# Son_of_Dark_Powersch.net
KiCad netlist of a schematic drawn in EAGLE
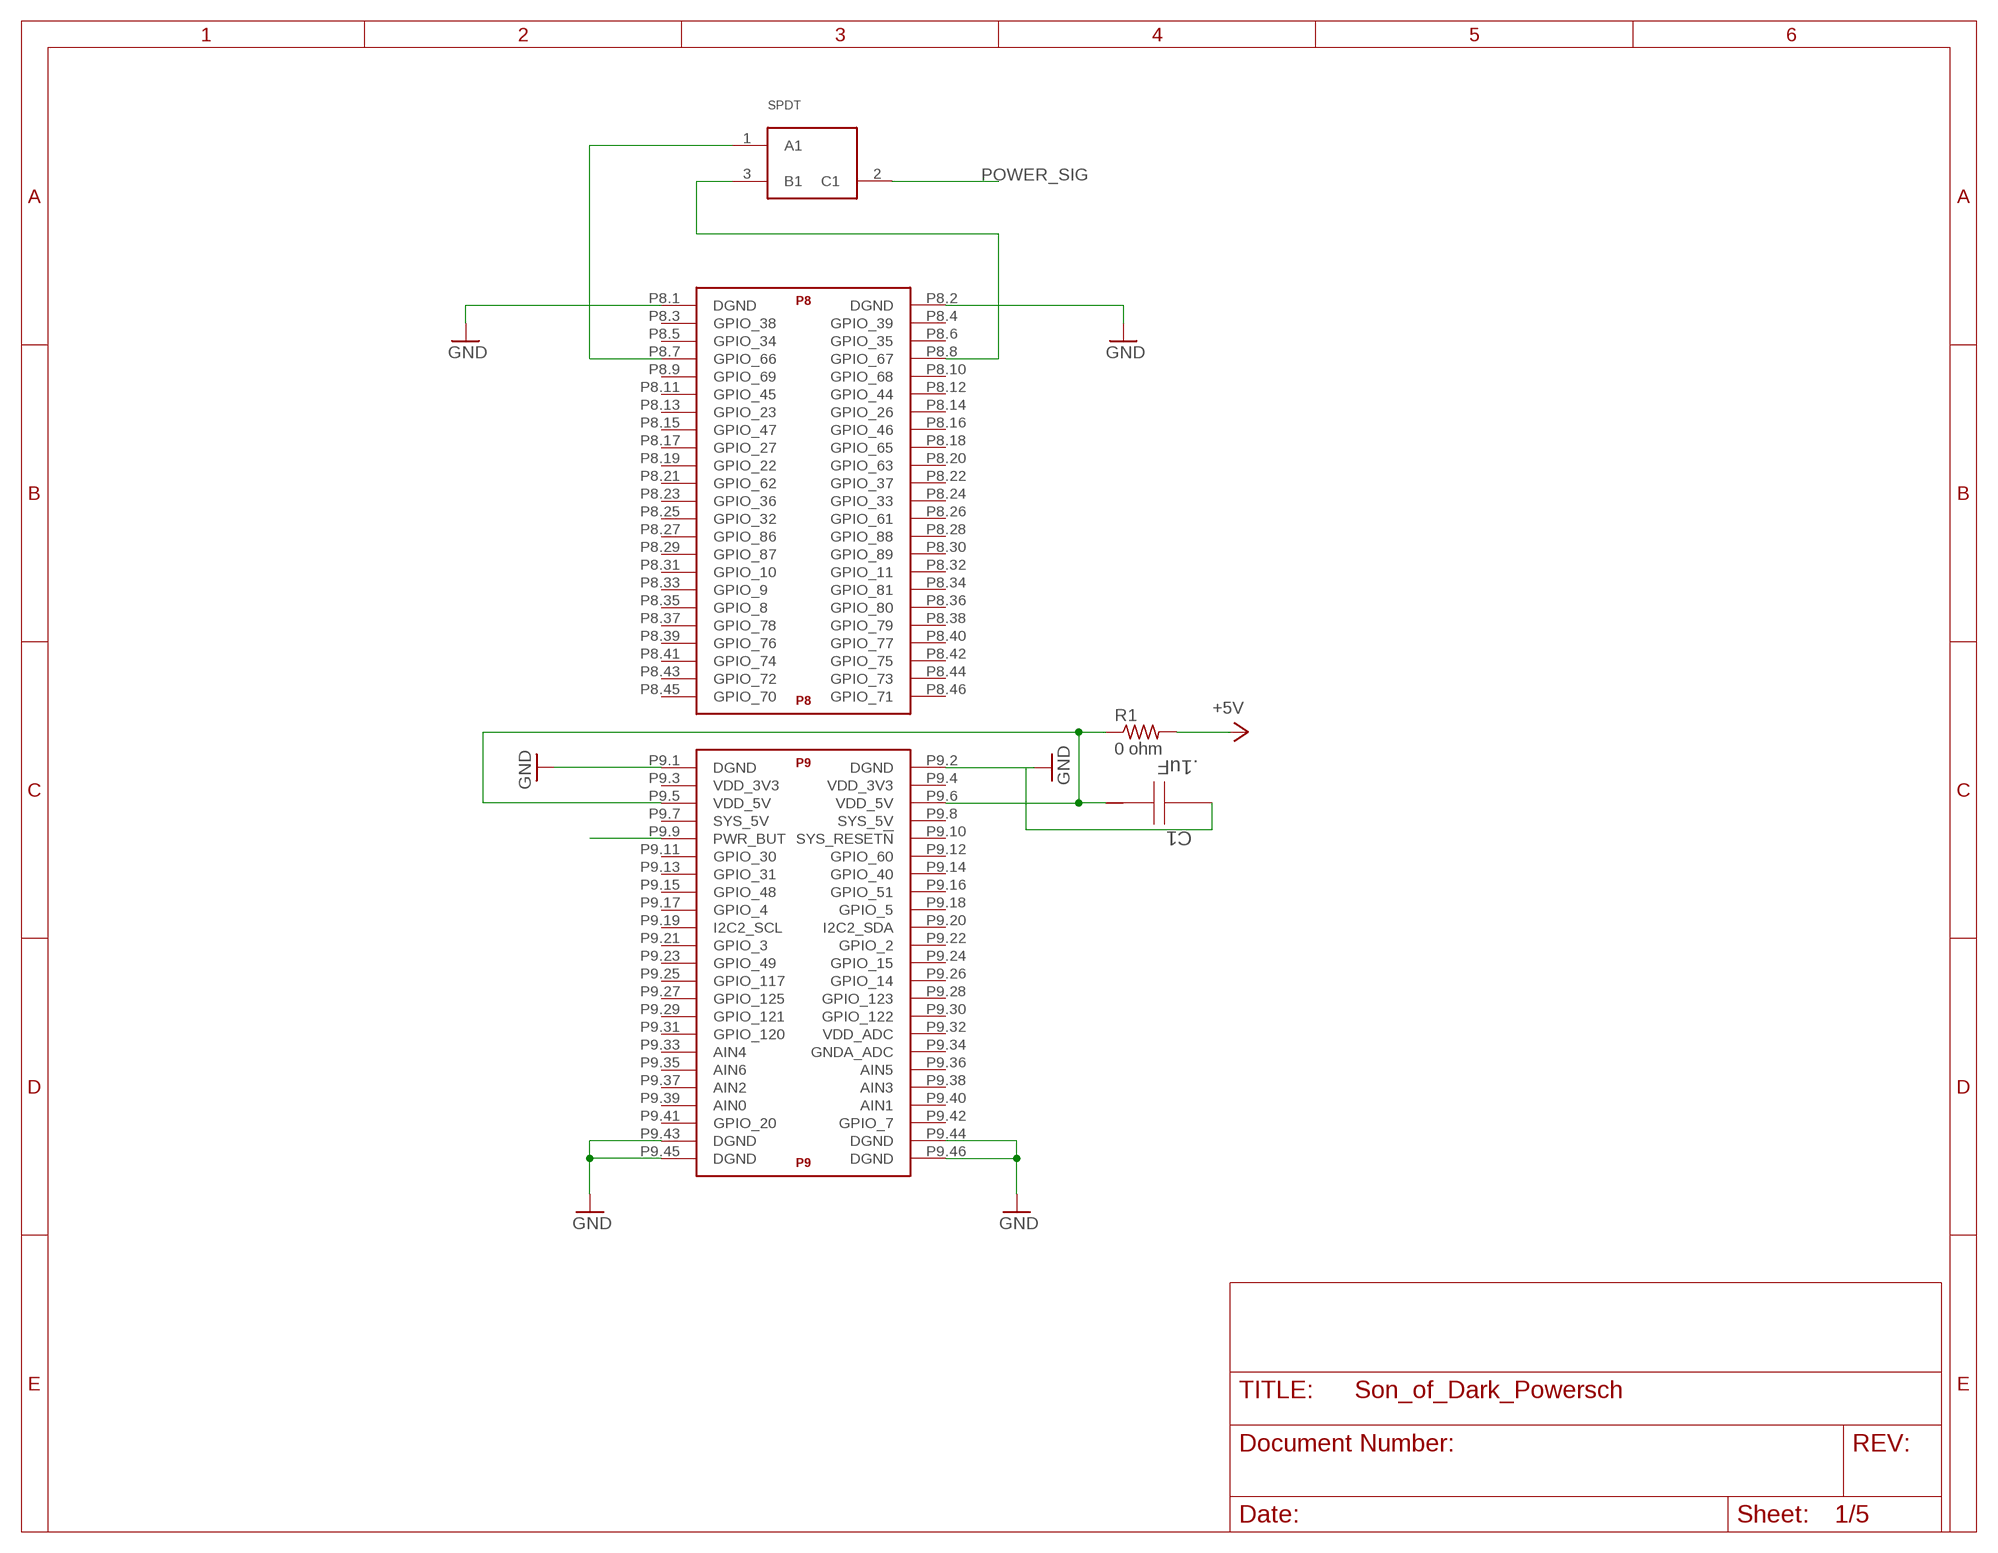
[diagram p0: schematic, sheet 1]
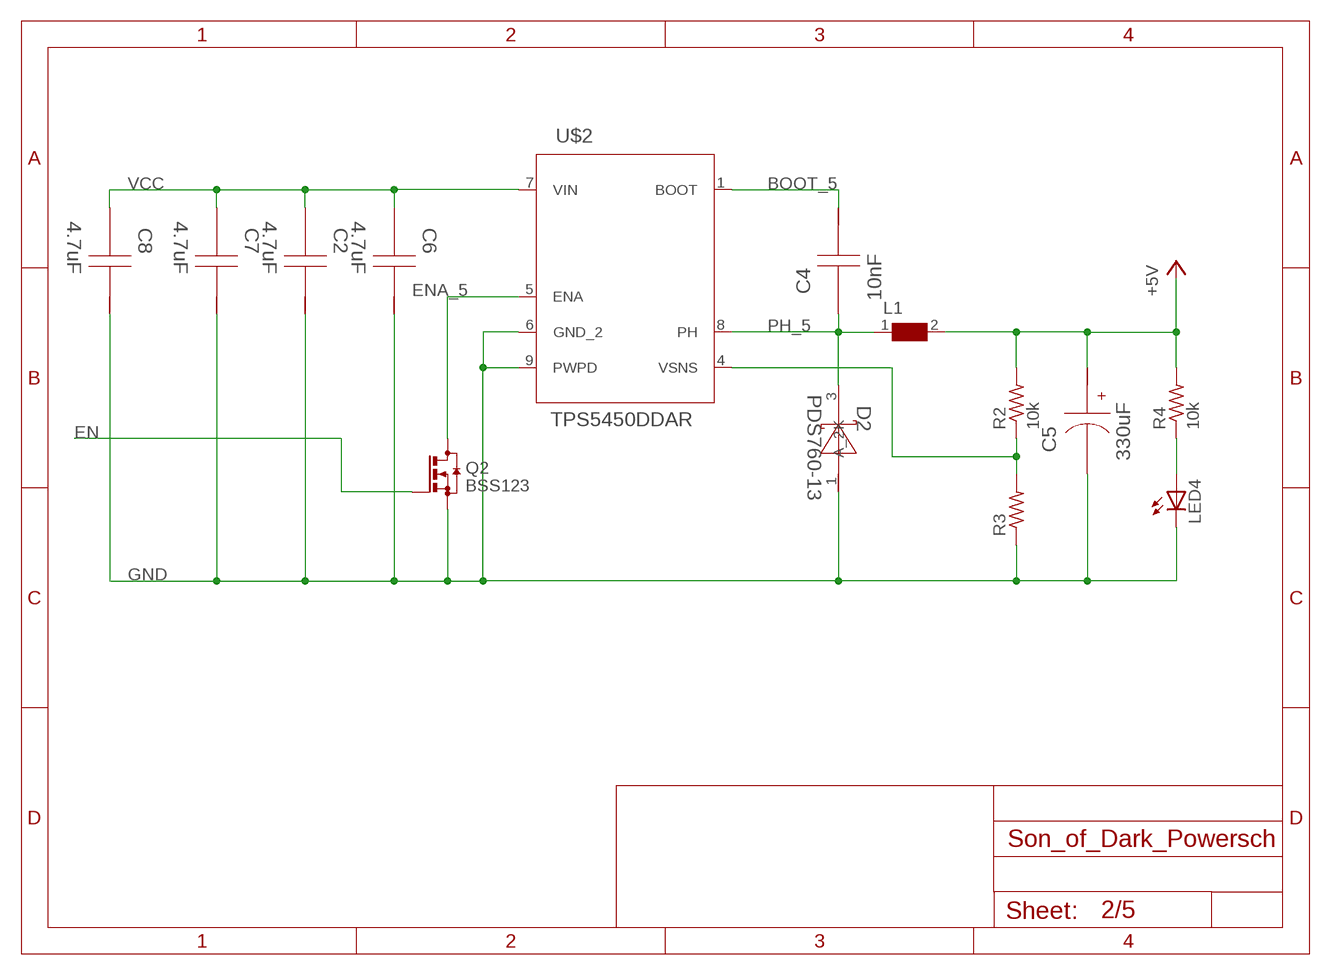
[diagram p1: schematic, sheet 2]
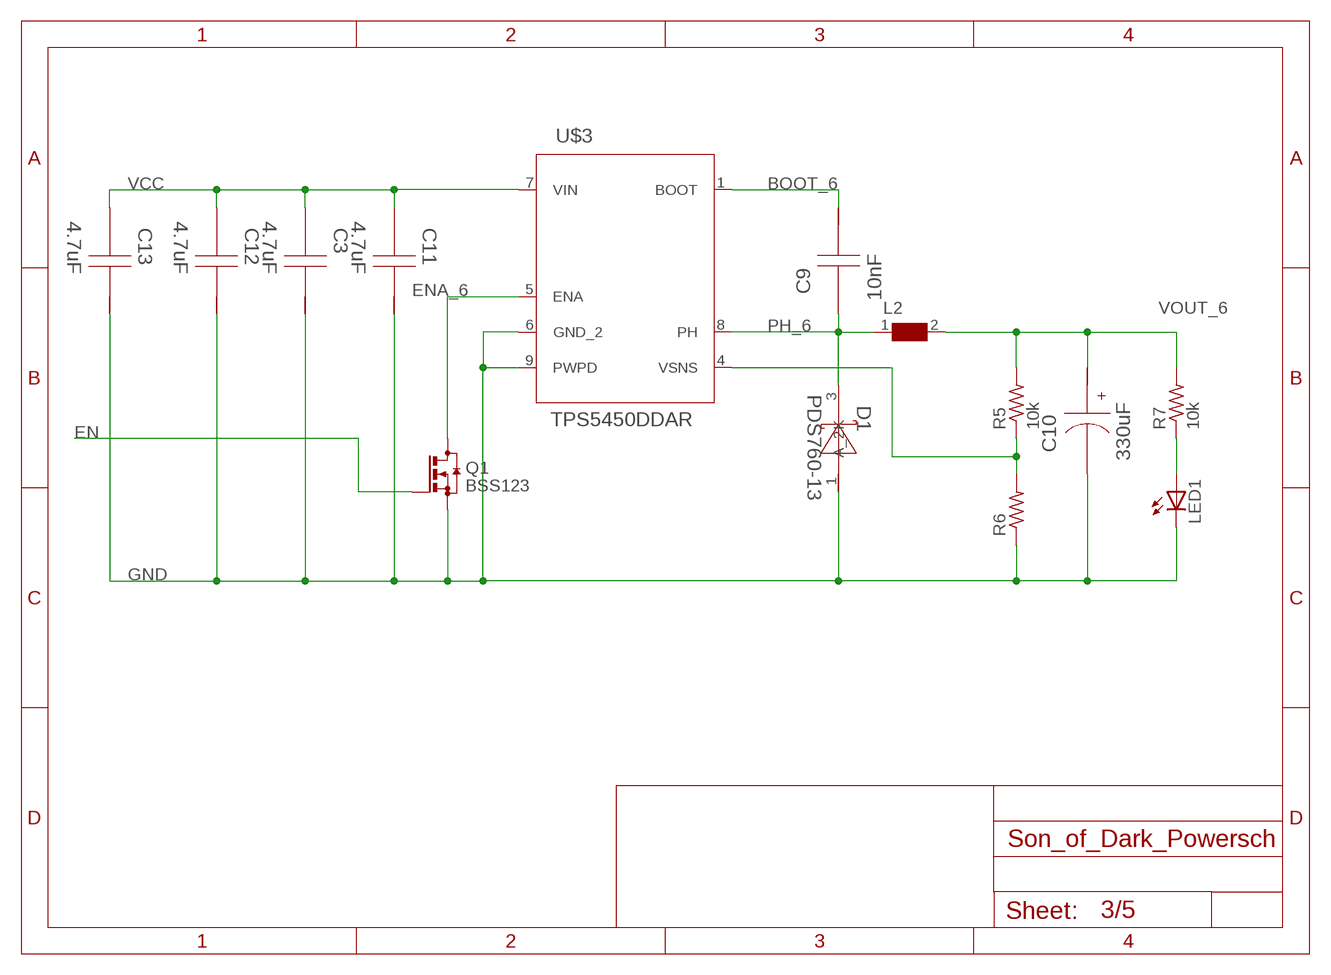
[diagram p2: schematic, sheet 3]
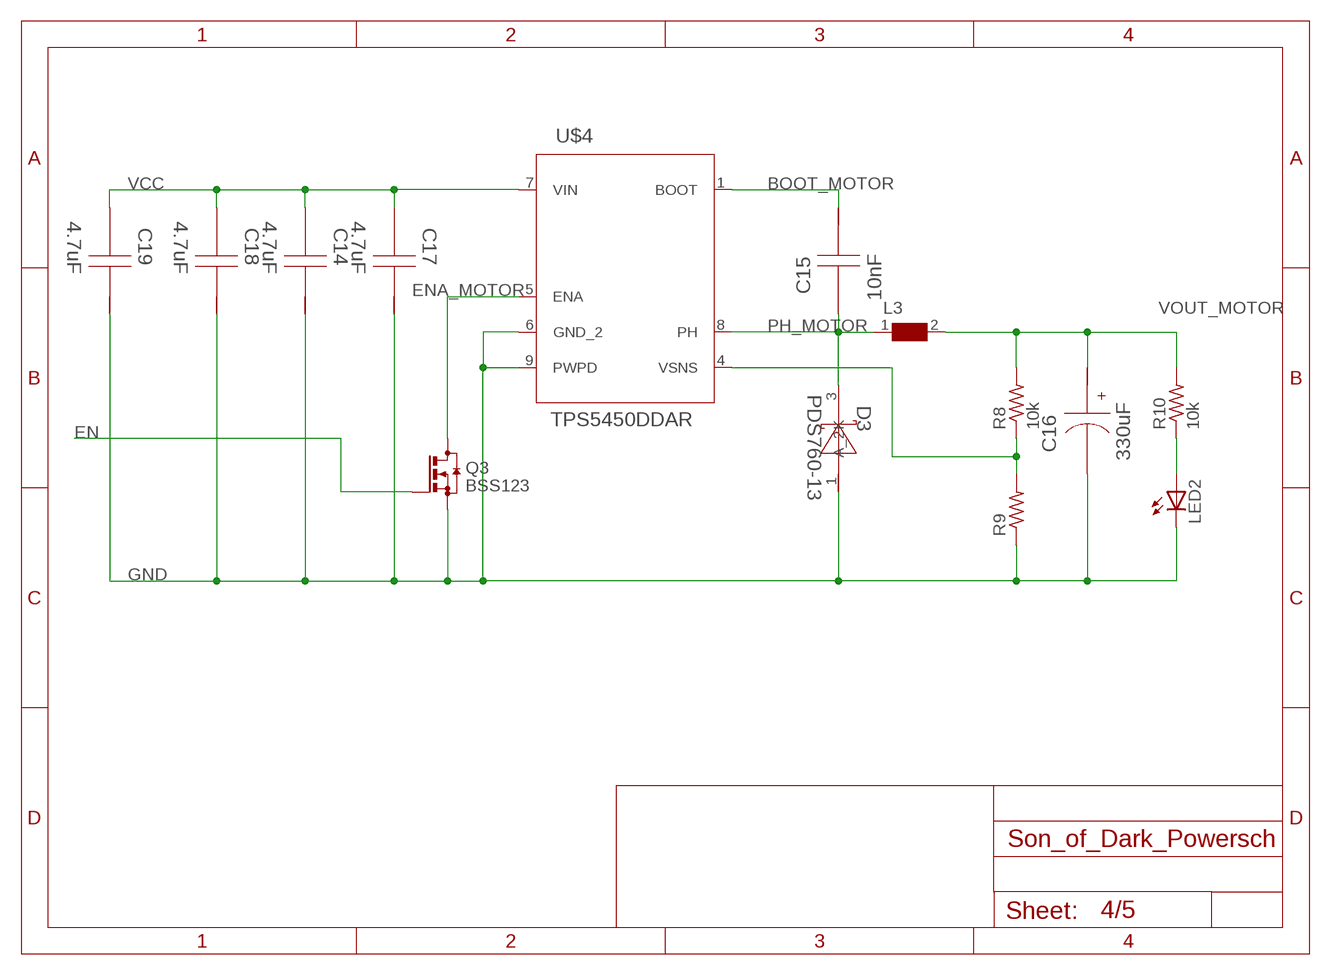
[diagram p3: schematic, sheet 4]
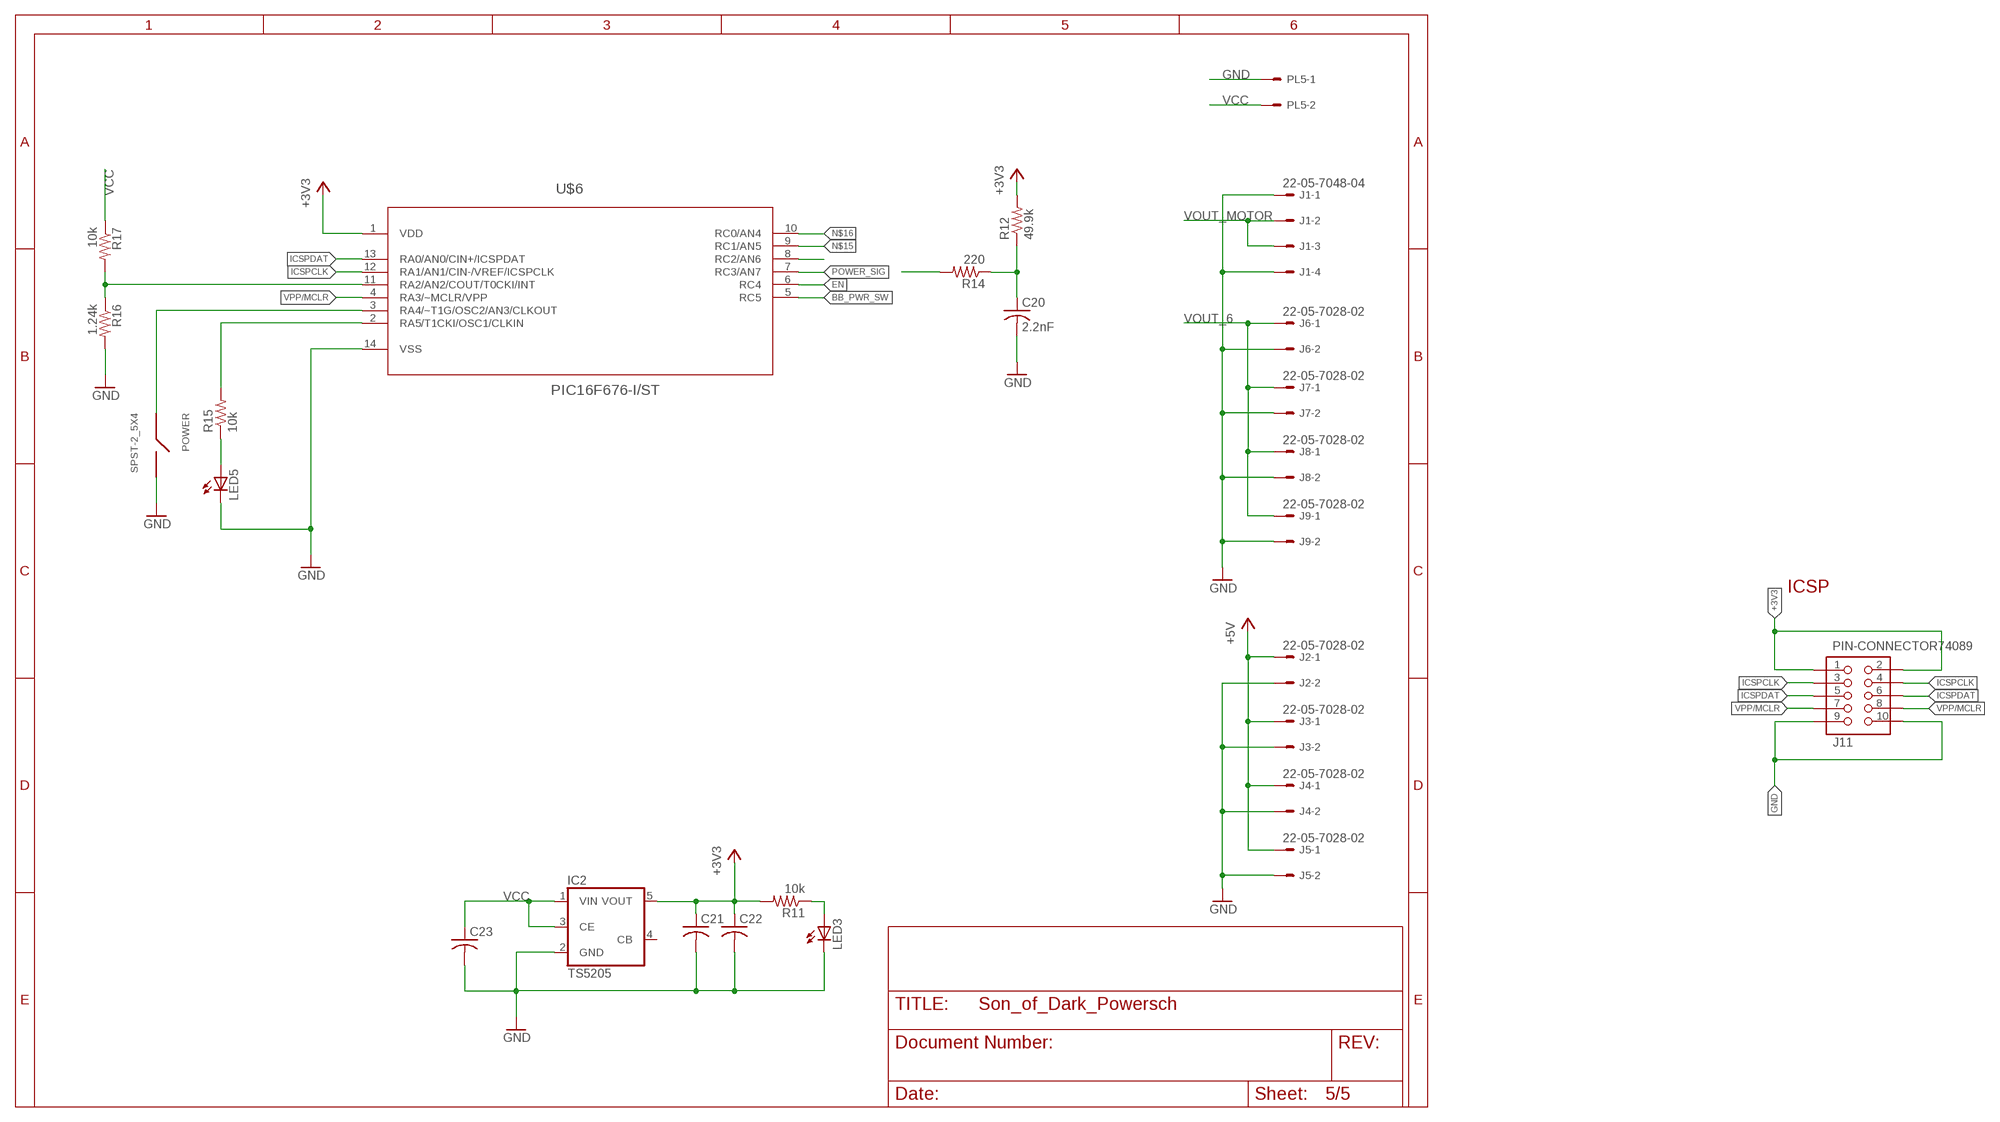
[diagram p4: schematic, sheet 5]

(export (version "E")
  (design (tool "Eeschema 10.0.6"))
  (components
    (comp (ref "C2")
      (value "4.7uF")
      (footprint "eagle-import:1206")
      (fields (field (name "MANUFACTURER_PART_NUMBER") "GRM31CR71H475KA12L"))
      (libsource (lib "eagle-import") (part "GRM31CR71H475KA12L"))
    )
    (comp (ref "C4")
      (value "10nF")
      (footprint "eagle-import:0805")
      (fields (field (name "MANUFACTURER_PART_NUMBER") "C0805C103K5RACTU"))
      (libsource (lib "eagle-import") (part "C0805C103K5RACTU"))
    )
    (comp (ref "C5")
      (value "330uF")
      (footprint "eagle-import:SM_RADIAL_10AMM")
      (fields (field (name "MANUFACTURER_PART_NUMBER") "10SVP330MX"))
      (libsource (lib "eagle-import") (part "10SVP330MX"))
    )
    (comp (ref "C6")
      (value "4.7uF")
      (footprint "eagle-import:1206")
      (fields (field (name "MANUFACTURER_PART_NUMBER") "GRM31CR71H475KA12L"))
      (libsource (lib "eagle-import") (part "GRM31CR71H475KA12L"))
    )
    (comp (ref "C7")
      (value "4.7uF")
      (footprint "eagle-import:1206")
      (fields (field (name "MANUFACTURER_PART_NUMBER") "GRM31CR71H475KA12L"))
      (libsource (lib "eagle-import") (part "GRM31CR71H475KA12L"))
    )
    (comp (ref "C8")
      (value "4.7uF")
      (footprint "eagle-import:1206")
      (fields (field (name "MANUFACTURER_PART_NUMBER") "GRM31CR71H475KA12L"))
      (libsource (lib "eagle-import") (part "GRM31CR71H475KA12L"))
    )
    (comp (ref "D2")
      (value "PDS760-13")
      (footprint "eagle-import:POWERDI5")
      (libsource (lib "eagle-import") (part "PDS760-13"))
    )
    (comp (ref "L1")
      (value "WE-HCC-7443331000_1090")
      (footprint "eagle-import:WE-HCC_1090")
      (fields (field (name "MPN") "7443331000"))
      (libsource (lib "eagle-import") (part "WE-HCC_1090-7443331000"))
    )
    (comp (ref "LED4")
      (value "LEDSML1206")
      (footprint "eagle-import:SML1206")
      (libsource (lib "eagle-import") (part "LEDSML1206"))
    )
    (comp (ref "Q2")
      (value "BSS123")
      (footprint "eagle-import:SOT23")
      (libsource (lib "eagle-import") (part "BSS123"))
    )
    (comp (ref "R2")
      (value "10k")
      (footprint "eagle-import:R1206")
      (libsource (lib "eagle-import") (part "R-US_R1206"))
    )
    (comp (ref "R3")
      (value "R-US_R1206")
      (footprint "eagle-import:R1206")
      (libsource (lib "eagle-import") (part "R-US_R1206"))
    )
    (comp (ref "R4")
      (value "10k")
      (footprint "eagle-import:R1206")
      (libsource (lib "eagle-import") (part "R-US_R1206"))
    )
    (comp (ref "U$2")
      (value "TPS5450DDAR")
      (footprint "eagle-import:R-PDSO-G8")
      (fields (field (name "MANUFACTURER_PART_NUMBER") "TPS5450DDA"))
      (libsource (lib "eagle-import") (part "TPS5450DDAR"))
    )
    (comp (ref "C3")
      (value "4.7uF")
      (footprint "eagle-import:1206")
      (fields (field (name "MANUFACTURER_PART_NUMBER") "GRM31CR71H475KA12L"))
      (libsource (lib "eagle-import") (part "GRM31CR71H475KA12L"))
    )
    (comp (ref "C9")
      (value "10nF")
      (footprint "eagle-import:0805")
      (fields (field (name "MANUFACTURER_PART_NUMBER") "C0805C103K5RACTU"))
      (libsource (lib "eagle-import") (part "C0805C103K5RACTU"))
    )
    (comp (ref "C10")
      (value "330uF")
      (footprint "eagle-import:SM_RADIAL_10AMM")
      (fields (field (name "MANUFACTURER_PART_NUMBER") "10SVP330MX"))
      (libsource (lib "eagle-import") (part "10SVP330MX"))
    )
    (comp (ref "C11")
      (value "4.7uF")
      (footprint "eagle-import:1206")
      (fields (field (name "MANUFACTURER_PART_NUMBER") "GRM31CR71H475KA12L"))
      (libsource (lib "eagle-import") (part "GRM31CR71H475KA12L"))
    )
    (comp (ref "C12")
      (value "4.7uF")
      (footprint "eagle-import:1206")
      (fields (field (name "MANUFACTURER_PART_NUMBER") "GRM31CR71H475KA12L"))
      (libsource (lib "eagle-import") (part "GRM31CR71H475KA12L"))
    )
    (comp (ref "C13")
      (value "4.7uF")
      (footprint "eagle-import:1206")
      (fields (field (name "MANUFACTURER_PART_NUMBER") "GRM31CR71H475KA12L"))
      (libsource (lib "eagle-import") (part "GRM31CR71H475KA12L"))
    )
    (comp (ref "D1")
      (value "PDS760-13")
      (footprint "eagle-import:POWERDI5")
      (libsource (lib "eagle-import") (part "PDS760-13"))
    )
    (comp (ref "L2")
      (value "WE-HCC-7443331000_1090")
      (footprint "eagle-import:WE-HCC_1090")
      (fields (field (name "MPN") "7443331000"))
      (libsource (lib "eagle-import") (part "WE-HCC_1090-7443331000"))
    )
    (comp (ref "LED1")
      (value "LEDSML1206")
      (footprint "eagle-import:SML1206")
      (libsource (lib "eagle-import") (part "LEDSML1206"))
    )
    (comp (ref "Q1")
      (value "BSS123")
      (footprint "eagle-import:SOT23")
      (libsource (lib "eagle-import") (part "BSS123"))
    )
    (comp (ref "R5")
      (value "10k")
      (footprint "eagle-import:R1206")
      (libsource (lib "eagle-import") (part "R-US_R1206"))
    )
    (comp (ref "R6")
      (value "R-US_R1206")
      (footprint "eagle-import:R1206")
      (libsource (lib "eagle-import") (part "R-US_R1206"))
    )
    (comp (ref "R7")
      (value "10k")
      (footprint "eagle-import:R1206")
      (libsource (lib "eagle-import") (part "R-US_R1206"))
    )
    (comp (ref "U$3")
      (value "TPS5450DDAR")
      (footprint "eagle-import:R-PDSO-G8")
      (fields (field (name "MANUFACTURER_PART_NUMBER") "TPS5450DDA"))
      (libsource (lib "eagle-import") (part "TPS5450DDAR"))
    )
    (comp (ref "C20")
      (value "2.2nF")
      (footprint "eagle-import:C0603")
      (libsource (lib "eagle-import") (part "C-USC0603"))
    )
    (comp (ref "C21")
      (value "C-USC0603")
      (footprint "eagle-import:C0603")
      (libsource (lib "eagle-import") (part "C-USC0603"))
    )
    (comp (ref "C22")
      (value "C-USC0603")
      (footprint "eagle-import:C0603")
      (libsource (lib "eagle-import") (part "C-USC0603"))
    )
    (comp (ref "C23")
      (value "C-USC0603")
      (footprint "eagle-import:C0603")
      (libsource (lib "eagle-import") (part "C-USC0603"))
    )
    (comp (ref "IC2")
      (value "TS5205")
      (footprint "eagle-import:SOT25")
      (libsource (lib "eagle-import") (part "TS5205"))
    )
    (comp (ref "J1")
      (value "22-05-7048-04")
      (footprint "eagle-import:7395-04")
      (libsource (lib "eagle-import") (part "22-?-0405-7048"))
    )
    (comp (ref "J2")
      (value "22-05-7028-02")
      (footprint "eagle-import:7395-02")
      (libsource (lib "eagle-import") (part "22-?-0205-7028"))
    )
    (comp (ref "J3")
      (value "22-05-7028-02")
      (footprint "eagle-import:7395-02")
      (libsource (lib "eagle-import") (part "22-?-0205-7028"))
    )
    (comp (ref "J4")
      (value "22-05-7028-02")
      (footprint "eagle-import:7395-02")
      (libsource (lib "eagle-import") (part "22-?-0205-7028"))
    )
    (comp (ref "J5")
      (value "22-05-7028-02")
      (footprint "eagle-import:7395-02")
      (libsource (lib "eagle-import") (part "22-?-0205-7028"))
    )
    (comp (ref "J6")
      (value "22-05-7028-02")
      (footprint "eagle-import:7395-02")
      (libsource (lib "eagle-import") (part "22-?-0205-7028"))
    )
    (comp (ref "J7")
      (value "22-05-7028-02")
      (footprint "eagle-import:7395-02")
      (libsource (lib "eagle-import") (part "22-?-0205-7028"))
    )
    (comp (ref "J8")
      (value "22-05-7028-02")
      (footprint "eagle-import:7395-02")
      (libsource (lib "eagle-import") (part "22-?-0205-7028"))
    )
    (comp (ref "J9")
      (value "22-05-7028-02")
      (footprint "eagle-import:7395-02")
      (libsource (lib "eagle-import") (part "22-?-0205-7028"))
    )
    (comp (ref "J11")
      (value "PIN-CONNECTOR74089")
      (footprint "eagle-import:10-PIN-SMD")
      (libsource (lib "eagle-import") (part "PIN-CONNECTOR74089"))
    )
    (comp (ref "LED3")
      (value "LEDSML1206")
      (footprint "eagle-import:SML1206")
      (libsource (lib "eagle-import") (part "LEDSML1206"))
    )
    (comp (ref "LED5")
      (value "LEDSML1206")
      (footprint "eagle-import:SML1206")
      (libsource (lib "eagle-import") (part "LEDSML1206"))
    )
    (comp (ref "PL5")
      (value "555X-2H")
      (footprint "eagle-import:5569-2")
      (libsource (lib "eagle-import") (part "555X-2H"))
    )
    (comp (ref "POWER")
      (value "SPST-2_5X4")
      (footprint "eagle-import:SPST-TAC-4X2_5MM")
      (libsource (lib "eagle-import") (part "SPST-2_5X4"))
    )
    (comp (ref "R11")
      (value "10k")
      (footprint "eagle-import:R1206")
      (libsource (lib "eagle-import") (part "R-US_R1206"))
    )
    (comp (ref "R12")
      (value "49.9k")
      (footprint "eagle-import:R0603")
      (libsource (lib "eagle-import") (part "R-US_R0603"))
    )
    (comp (ref "R14")
      (value "220")
      (footprint "eagle-import:R0603")
      (libsource (lib "eagle-import") (part "R-US_R0603"))
    )
    (comp (ref "R15")
      (value "10k")
      (footprint "eagle-import:R1206")
      (libsource (lib "eagle-import") (part "R-US_R1206"))
    )
    (comp (ref "R16")
      (value "1.24k")
      (footprint "eagle-import:R0603")
      (libsource (lib "eagle-import") (part "R-US_R0603"))
    )
    (comp (ref "R17")
      (value "10k")
      (footprint "eagle-import:R0603")
      (libsource (lib "eagle-import") (part "R-US_R0603"))
    )
    (comp (ref "U$6")
      (value "PIC16F676-I/ST")
      (footprint "eagle-import:SOP65P640X120-14N")
      (libsource (lib "eagle-import") (part "PIC16F676-I/ST"))
    )
    (comp (ref "C1")
      (value ".1uF")
      (footprint "eagle-import:1206")
      (fields (field (name "MANUFACTURER_PART_NUMBER") "C3216X5R1A106K"))
      (libsource (lib "eagle-import") (part "C3216X5R1A106K"))
    )
    (comp (ref "R1")
      (value "0 ohm")
      (footprint "eagle-import:R1206")
      (libsource (lib "eagle-import") (part "R-US_R1206"))
    )
    (comp (ref "SPDT")
      (value "SPDT_SWITCH")
      (footprint "eagle-import:SPDT")
      (libsource (lib "eagle-import") (part "SPDT_SWITCH"))
    )
    (comp (ref "U$1")
      (value "BEAGLE_BONE_BLACK_CAPE")
      (footprint "eagle-import:BEAGLE_BONE_BLACK_CAPE")
      (libsource (lib "eagle-import") (part "BEAGLE_BONE_BLACK_CAPE"))
    )
    (comp (ref "C14")
      (value "4.7uF")
      (footprint "eagle-import:1206")
      (fields (field (name "MANUFACTURER_PART_NUMBER") "GRM31CR71H475KA12L"))
      (libsource (lib "eagle-import") (part "GRM31CR71H475KA12L"))
    )
    (comp (ref "C15")
      (value "10nF")
      (footprint "eagle-import:0805")
      (fields (field (name "MANUFACTURER_PART_NUMBER") "C0805C103K5RACTU"))
      (libsource (lib "eagle-import") (part "C0805C103K5RACTU"))
    )
    (comp (ref "C16")
      (value "330uF")
      (footprint "eagle-import:SM_RADIAL_10AMM")
      (fields (field (name "MANUFACTURER_PART_NUMBER") "10SVP330MX"))
      (libsource (lib "eagle-import") (part "10SVP330MX"))
    )
    (comp (ref "C17")
      (value "4.7uF")
      (footprint "eagle-import:1206")
      (fields (field (name "MANUFACTURER_PART_NUMBER") "GRM31CR71H475KA12L"))
      (libsource (lib "eagle-import") (part "GRM31CR71H475KA12L"))
    )
    (comp (ref "C18")
      (value "4.7uF")
      (footprint "eagle-import:1206")
      (fields (field (name "MANUFACTURER_PART_NUMBER") "GRM31CR71H475KA12L"))
      (libsource (lib "eagle-import") (part "GRM31CR71H475KA12L"))
    )
    (comp (ref "C19")
      (value "4.7uF")
      (footprint "eagle-import:1206")
      (fields (field (name "MANUFACTURER_PART_NUMBER") "GRM31CR71H475KA12L"))
      (libsource (lib "eagle-import") (part "GRM31CR71H475KA12L"))
    )
    (comp (ref "D3")
      (value "PDS760-13")
      (footprint "eagle-import:POWERDI5")
      (libsource (lib "eagle-import") (part "PDS760-13"))
    )
    (comp (ref "L3")
      (value "WE-HCC-7443331000_1090")
      (footprint "eagle-import:WE-HCC_1090")
      (fields (field (name "MPN") "7443331000"))
      (libsource (lib "eagle-import") (part "WE-HCC_1090-7443331000"))
    )
    (comp (ref "LED2")
      (value "LEDSML1206")
      (footprint "eagle-import:SML1206")
      (libsource (lib "eagle-import") (part "LEDSML1206"))
    )
    (comp (ref "Q3")
      (value "BSS123")
      (footprint "eagle-import:SOT23")
      (libsource (lib "eagle-import") (part "BSS123"))
    )
    (comp (ref "R8")
      (value "10k")
      (footprint "eagle-import:R1206")
      (libsource (lib "eagle-import") (part "R-US_R1206"))
    )
    (comp (ref "R9")
      (value "R-US_R1206")
      (footprint "eagle-import:R1206")
      (libsource (lib "eagle-import") (part "R-US_R1206"))
    )
    (comp (ref "R10")
      (value "10k")
      (footprint "eagle-import:R1206")
      (libsource (lib "eagle-import") (part "R-US_R1206"))
    )
    (comp (ref "U$4")
      (value "TPS5450DDAR")
      (footprint "eagle-import:R-PDSO-G8")
      (fields (field (name "MANUFACTURER_PART_NUMBER") "TPS5450DDA"))
      (libsource (lib "eagle-import") (part "TPS5450DDAR"))
    )
  )
  (nets
    (net (code "1") (name "+3V3") (class "Default")
      (node (ref "C21") (pin "1") (pinfunction "1_1") (pintype "passive"))
      (node (ref "C22") (pin "1") (pinfunction "1_1") (pintype "passive"))
      (node (ref "IC2") (pin "5") (pinfunction "VOUT_5") (pintype "passive"))
      (node (ref "J11") (pin "1") (pinfunction "P$1_1") (pintype "power_in"))
      (node (ref "J11") (pin "2") (pinfunction "P$2_2") (pintype "power_in"))
      (node (ref "R11") (pin "2") (pinfunction "2_2") (pintype "passive"))
      (node (ref "R12") (pin "2") (pinfunction "2_2") (pintype "passive"))
      (node (ref "U$6") (pin "1") (pinfunction "VDD_1") (pintype "power_in"))
    )
    (net (code "2") (name "+5V") (class "Default")
      (node (ref "C5") (pin "1") (pinfunction "+_1") (pintype "passive"))
      (node (ref "J2") (pin "1") (pinfunction "S_1") (pintype "passive"))
      (node (ref "J3") (pin "1") (pinfunction "S_1") (pintype "passive"))
      (node (ref "J4") (pin "1") (pinfunction "S_1") (pintype "passive"))
      (node (ref "J5") (pin "1") (pinfunction "S_1") (pintype "passive"))
      (node (ref "L1") (pin "2") (pinfunction "2_2") (pintype "passive"))
      (node (ref "R1") (pin "2") (pinfunction "2_2") (pintype "passive"))
      (node (ref "R2") (pin "2") (pinfunction "2_2") (pintype "passive"))
      (node (ref "R4") (pin "2") (pinfunction "2_2") (pintype "passive"))
    )
    (net (code "3") (name "BB_PWR_SW") (class "Default")
      (node (ref "U$1") (pin "P9.9") (pinfunction "PWR_BUT_P9.9") (pintype "bidirectional"))
      (node (ref "U$6") (pin "5") (pinfunction "RC5_5") (pintype "bidirectional"))
    )
    (net (code "4") (name "BOOT_5") (class "Default")
      (node (ref "C4") (pin "1") (pinfunction "1_1") (pintype "passive"))
      (node (ref "U$2") (pin "1") (pinfunction "BOOT_1") (pintype "passive"))
    )
    (net (code "5") (name "BOOT_6") (class "Default")
      (node (ref "C9") (pin "1") (pinfunction "1_1") (pintype "passive"))
      (node (ref "U$3") (pin "1") (pinfunction "BOOT_1") (pintype "passive"))
    )
    (net (code "6") (name "BOOT_MOTOR") (class "Default")
      (node (ref "C15") (pin "1") (pinfunction "1_1") (pintype "passive"))
      (node (ref "U$4") (pin "1") (pinfunction "BOOT_1") (pintype "passive"))
    )
    (net (code "7") (name "EN") (class "Default")
      (node (ref "Q1") (pin "1") (pinfunction "G_1") (pintype "passive"))
      (node (ref "Q2") (pin "1") (pinfunction "G_1") (pintype "passive"))
      (node (ref "Q3") (pin "1") (pinfunction "G_1") (pintype "passive"))
      (node (ref "U$6") (pin "6") (pinfunction "RC4_6") (pintype "bidirectional"))
    )
    (net (code "8") (name "ENA_5") (class "Default")
      (node (ref "Q2") (pin "3") (pinfunction "D_3") (pintype "passive"))
      (node (ref "U$2") (pin "5") (pinfunction "ENA_5") (pintype "passive"))
    )
    (net (code "9") (name "ENA_6") (class "Default")
      (node (ref "Q1") (pin "3") (pinfunction "D_3") (pintype "passive"))
      (node (ref "U$3") (pin "5") (pinfunction "ENA_5") (pintype "passive"))
    )
    (net (code "10") (name "ENA_MOTOR") (class "Default")
      (node (ref "Q3") (pin "3") (pinfunction "D_3") (pintype "passive"))
      (node (ref "U$4") (pin "5") (pinfunction "ENA_5") (pintype "passive"))
    )
    (net (code "11") (name "GND") (class "Default")
      (node (ref "C1") (pin "2") (pinfunction "2_2") (pintype "passive"))
      (node (ref "C10") (pin "2") (pinfunction "-_2") (pintype "passive"))
      (node (ref "C11") (pin "1") (pinfunction "1_1") (pintype "passive"))
      (node (ref "C12") (pin "1") (pinfunction "1_1") (pintype "passive"))
      (node (ref "C13") (pin "1") (pinfunction "1_1") (pintype "passive"))
      (node (ref "C14") (pin "1") (pinfunction "1_1") (pintype "passive"))
      (node (ref "C16") (pin "2") (pinfunction "-_2") (pintype "passive"))
      (node (ref "C17") (pin "1") (pinfunction "1_1") (pintype "passive"))
      (node (ref "C18") (pin "1") (pinfunction "1_1") (pintype "passive"))
      (node (ref "C19") (pin "1") (pinfunction "1_1") (pintype "passive"))
      (node (ref "C2") (pin "1") (pinfunction "1_1") (pintype "passive"))
      (node (ref "C20") (pin "2") (pinfunction "2_2") (pintype "passive"))
      (node (ref "C21") (pin "2") (pinfunction "2_2") (pintype "passive"))
      (node (ref "C22") (pin "2") (pinfunction "2_2") (pintype "passive"))
      (node (ref "C23") (pin "2") (pinfunction "2_2") (pintype "passive"))
      (node (ref "C3") (pin "1") (pinfunction "1_1") (pintype "passive"))
      (node (ref "C5") (pin "2") (pinfunction "-_2") (pintype "passive"))
      (node (ref "C6") (pin "1") (pinfunction "1_1") (pintype "passive"))
      (node (ref "C7") (pin "1") (pinfunction "1_1") (pintype "passive"))
      (node (ref "C8") (pin "1") (pinfunction "1_1") (pintype "passive"))
      (node (ref "D1") (pin "1") (pinfunction "A_2_1") (pintype "passive"))
      (node (ref "D2") (pin "1") (pinfunction "A_2_1") (pintype "passive"))
      (node (ref "D3") (pin "1") (pinfunction "A_2_1") (pintype "passive"))
      (node (ref "IC2") (pin "2") (pinfunction "GND_2") (pintype "passive"))
      (node (ref "J1") (pin "1") (pinfunction "S_1") (pintype "passive"))
      (node (ref "J1") (pin "4") (pinfunction "S_4") (pintype "passive"))
      (node (ref "J11") (pin "10") (pinfunction "P$10_10") (pintype "power_in"))
      (node (ref "J11") (pin "9") (pinfunction "P$9_9") (pintype "power_in"))
      (node (ref "J2") (pin "2") (pinfunction "S_2") (pintype "passive"))
      (node (ref "J3") (pin "2") (pinfunction "S_2") (pintype "passive"))
      (node (ref "J4") (pin "2") (pinfunction "S_2") (pintype "passive"))
      (node (ref "J5") (pin "2") (pinfunction "S_2") (pintype "passive"))
      (node (ref "J6") (pin "2") (pinfunction "S_2") (pintype "passive"))
      (node (ref "J7") (pin "2") (pinfunction "S_2") (pintype "passive"))
      (node (ref "J8") (pin "2") (pinfunction "S_2") (pintype "passive"))
      (node (ref "J9") (pin "2") (pinfunction "S_2") (pintype "passive"))
      (node (ref "LED1") (pin "C") (pinfunction "C_C") (pintype "passive"))
      (node (ref "LED2") (pin "C") (pinfunction "C_C") (pintype "passive"))
      (node (ref "LED3") (pin "C") (pinfunction "C_C") (pintype "passive"))
      (node (ref "LED4") (pin "C") (pinfunction "C_C") (pintype "passive"))
      (node (ref "LED5") (pin "C") (pinfunction "C_C") (pintype "passive"))
      (node (ref "PL5") (pin "1") (pinfunction "S_1") (pintype "passive"))
      (node (ref "POWER") (pin "P$2") (pinfunction "P$2_P$2") (pintype "bidirectional"))
      (node (ref "Q1") (pin "2") (pinfunction "S_2") (pintype "passive"))
      (node (ref "Q2") (pin "2") (pinfunction "S_2") (pintype "passive"))
      (node (ref "Q3") (pin "2") (pinfunction "S_2") (pintype "passive"))
      (node (ref "R16") (pin "2") (pinfunction "2_2") (pintype "passive"))
      (node (ref "R3") (pin "1") (pinfunction "1_1") (pintype "passive"))
      (node (ref "R6") (pin "1") (pinfunction "1_1") (pintype "passive"))
      (node (ref "R9") (pin "1") (pinfunction "1_1") (pintype "passive"))
      (node (ref "U$1") (pin "P8.1") (pinfunction "DGND_P8.1") (pintype "bidirectional"))
      (node (ref "U$1") (pin "P8.2") (pinfunction "DGND_P8.2") (pintype "bidirectional"))
      (node (ref "U$1") (pin "P9.1") (pinfunction "DGND_P9.1") (pintype "bidirectional"))
      (node (ref "U$1") (pin "P9.2") (pinfunction "DGND_P9.2") (pintype "bidirectional"))
      (node (ref "U$1") (pin "P9.43") (pinfunction "DGND_P9.43") (pintype "bidirectional"))
      (node (ref "U$1") (pin "P9.44") (pinfunction "DGND_P9.44") (pintype "bidirectional"))
      (node (ref "U$1") (pin "P9.45") (pinfunction "DGND_P9.45") (pintype "bidirectional"))
      (node (ref "U$1") (pin "P9.46") (pinfunction "DGND_P9.46") (pintype "bidirectional"))
      (node (ref "U$2") (pin "6") (pinfunction "GND_2_6") (pintype "passive"))
      (node (ref "U$2") (pin "9") (pinfunction "PWPD_9") (pintype "passive"))
      (node (ref "U$3") (pin "6") (pinfunction "GND_2_6") (pintype "passive"))
      (node (ref "U$3") (pin "9") (pinfunction "PWPD_9") (pintype "passive"))
      (node (ref "U$4") (pin "6") (pinfunction "GND_2_6") (pintype "passive"))
      (node (ref "U$4") (pin "9") (pinfunction "PWPD_9") (pintype "passive"))
      (node (ref "U$6") (pin "14") (pinfunction "VSS_14") (pintype "power_in"))
    )
    (net (code "12") (name "ICSPCLK") (class "Default")
      (node (ref "J11") (pin "3") (pinfunction "P$3_3") (pintype "power_in"))
      (node (ref "J11") (pin "4") (pinfunction "P$4_4") (pintype "power_in"))
      (node (ref "U$6") (pin "12") (pinfunction "RA1/AN1/CIN-/VREF/ICSPCLK_12") (pintype "bidirectional"))
    )
    (net (code "13") (name "ICSPDAT") (class "Default")
      (node (ref "J11") (pin "5") (pinfunction "P$5_5") (pintype "power_in"))
      (node (ref "J11") (pin "6") (pinfunction "P$6_6") (pintype "power_in"))
      (node (ref "U$6") (pin "13") (pinfunction "RA0/AN0/CIN+/ICSPDAT_13") (pintype "bidirectional"))
    )
    (net (code "14") (name "N$15") (class "Default")
      (node (ref "U$6") (pin "9") (pinfunction "RC1/AN5_9") (pintype "bidirectional"))
    )
    (net (code "15") (name "N$16") (class "Default")
      (node (ref "U$6") (pin "10") (pinfunction "RC0/AN4_10") (pintype "bidirectional"))
    )
    (net (code "16") (name "Net-(C1-Pad1)") (class "Default")
      (node (ref "C1") (pin "1") (pinfunction "1_1") (pintype "passive"))
      (node (ref "R1") (pin "1") (pinfunction "1_1") (pintype "passive"))
      (node (ref "U$1") (pin "P9.5") (pinfunction "VDD_5V_P9.5") (pintype "bidirectional"))
      (node (ref "U$1") (pin "P9.6") (pinfunction "VDD_5V_P9.6") (pintype "bidirectional"))
    )
    (net (code "17") (name "Net-(C20-Pad1)") (class "Default")
      (node (ref "C20") (pin "1") (pinfunction "1_1") (pintype "passive"))
      (node (ref "R12") (pin "1") (pinfunction "1_1") (pintype "passive"))
      (node (ref "R14") (pin "1") (pinfunction "1_1") (pintype "passive"))
    )
    (net (code "18") (name "Net-(LED1-PadA)") (class "Default")
      (node (ref "LED1") (pin "A") (pinfunction "A_A") (pintype "passive"))
      (node (ref "R7") (pin "1") (pinfunction "1_1") (pintype "passive"))
    )
    (net (code "19") (name "Net-(LED2-PadA)") (class "Default")
      (node (ref "LED2") (pin "A") (pinfunction "A_A") (pintype "passive"))
      (node (ref "R10") (pin "1") (pinfunction "1_1") (pintype "passive"))
    )
    (net (code "20") (name "Net-(LED3-PadA)") (class "Default")
      (node (ref "LED3") (pin "A") (pinfunction "A_A") (pintype "passive"))
      (node (ref "R11") (pin "1") (pinfunction "1_1") (pintype "passive"))
    )
    (net (code "21") (name "Net-(LED4-PadA)") (class "Default")
      (node (ref "LED4") (pin "A") (pinfunction "A_A") (pintype "passive"))
      (node (ref "R4") (pin "1") (pinfunction "1_1") (pintype "passive"))
    )
    (net (code "22") (name "Net-(LED5-PadA)") (class "Default")
      (node (ref "LED5") (pin "A") (pinfunction "A_A") (pintype "passive"))
      (node (ref "R15") (pin "1") (pinfunction "1_1") (pintype "passive"))
    )
    (net (code "23") (name "Net-(SPDT-A1)") (class "Default")
      (node (ref "SPDT") (pin "1") (pinfunction "A1_1") (pintype "bidirectional"))
      (node (ref "U$1") (pin "P8.7") (pinfunction "GPIO_66_P8.7") (pintype "bidirectional"))
    )
    (net (code "24") (name "Net-(SPDT-B1)") (class "Default")
      (node (ref "SPDT") (pin "3") (pinfunction "B1_3") (pintype "bidirectional"))
      (node (ref "U$1") (pin "P8.8") (pinfunction "GPIO_67_P8.8") (pintype "bidirectional"))
    )
    (net (code "25") (name "Net-(U$2-VSNS)") (class "Default")
      (node (ref "R2") (pin "1") (pinfunction "1_1") (pintype "passive"))
      (node (ref "R3") (pin "2") (pinfunction "2_2") (pintype "passive"))
      (node (ref "U$2") (pin "4") (pinfunction "VSNS_4") (pintype "passive"))
    )
    (net (code "26") (name "Net-(U$3-VSNS)") (class "Default")
      (node (ref "R5") (pin "1") (pinfunction "1_1") (pintype "passive"))
      (node (ref "R6") (pin "2") (pinfunction "2_2") (pintype "passive"))
      (node (ref "U$3") (pin "4") (pinfunction "VSNS_4") (pintype "passive"))
    )
    (net (code "27") (name "Net-(U$4-VSNS)") (class "Default")
      (node (ref "R8") (pin "1") (pinfunction "1_1") (pintype "passive"))
      (node (ref "R9") (pin "2") (pinfunction "2_2") (pintype "passive"))
      (node (ref "U$4") (pin "4") (pinfunction "VSNS_4") (pintype "passive"))
    )
    (net (code "28") (name "Net-(U$6-RA2{slash}AN2{slash}COUT{slash}T0CKI{slash}INT)") (class "Default")
      (node (ref "R16") (pin "1") (pinfunction "1_1") (pintype "passive"))
      (node (ref "R17") (pin "2") (pinfunction "2_2") (pintype "passive"))
      (node (ref "U$6") (pin "11") (pinfunction "RA2/AN2/COUT/T0CKI/INT_11") (pintype "bidirectional"))
    )
    (net (code "29") (name "Net-(U$6-RA4{slash}~{T1G{slash}OSC2{slash}AN3{slash}CLKOUT})") (class "Default")
      (node (ref "POWER") (pin "P$1") (pinfunction "P$1_P$1") (pintype "bidirectional"))
      (node (ref "U$6") (pin "3") (pinfunction "RA4/~{T1G/OSC2/AN3/CLKOUT}_3") (pintype "bidirectional"))
    )
    (net (code "30") (name "Net-(U$6-RA5{slash}T1CKI{slash}OSC1{slash}CLKIN)") (class "Default")
      (node (ref "R15") (pin "2") (pinfunction "2_2") (pintype "passive"))
      (node (ref "U$6") (pin "2") (pinfunction "RA5/T1CKI/OSC1/CLKIN_2") (pintype "bidirectional"))
    )
    (net (code "31") (name "PH_5") (class "Default")
      (node (ref "C4") (pin "2") (pinfunction "2_2") (pintype "passive"))
      (node (ref "D2") (pin "3") (pinfunction "K_3") (pintype "passive"))
      (node (ref "L1") (pin "1") (pinfunction "1_1") (pintype "passive"))
      (node (ref "U$2") (pin "8") (pinfunction "PH_8") (pintype "passive"))
    )
    (net (code "32") (name "PH_6") (class "Default")
      (node (ref "C9") (pin "2") (pinfunction "2_2") (pintype "passive"))
      (node (ref "D1") (pin "3") (pinfunction "K_3") (pintype "passive"))
      (node (ref "L2") (pin "1") (pinfunction "1_1") (pintype "passive"))
      (node (ref "U$3") (pin "8") (pinfunction "PH_8") (pintype "passive"))
    )
    (net (code "33") (name "PH_MOTOR") (class "Default")
      (node (ref "C15") (pin "2") (pinfunction "2_2") (pintype "passive"))
      (node (ref "D3") (pin "3") (pinfunction "K_3") (pintype "passive"))
      (node (ref "L3") (pin "1") (pinfunction "1_1") (pintype "passive"))
      (node (ref "U$4") (pin "8") (pinfunction "PH_8") (pintype "passive"))
    )
    (net (code "34") (name "POWER_SIG") (class "Default")
      (node (ref "SPDT") (pin "2") (pinfunction "C1_2") (pintype "bidirectional"))
      (node (ref "U$6") (pin "7") (pinfunction "RC3/AN7_7") (pintype "bidirectional"))
    )
    (net (code "35") (name "VCC") (class "Default")
      (node (ref "C11") (pin "2") (pinfunction "2_2") (pintype "passive"))
      (node (ref "C12") (pin "2") (pinfunction "2_2") (pintype "passive"))
      (node (ref "C13") (pin "2") (pinfunction "2_2") (pintype "passive"))
      (node (ref "C14") (pin "2") (pinfunction "2_2") (pintype "passive"))
      (node (ref "C17") (pin "2") (pinfunction "2_2") (pintype "passive"))
      (node (ref "C18") (pin "2") (pinfunction "2_2") (pintype "passive"))
      (node (ref "C19") (pin "2") (pinfunction "2_2") (pintype "passive"))
      (node (ref "C2") (pin "2") (pinfunction "2_2") (pintype "passive"))
      (node (ref "C23") (pin "1") (pinfunction "1_1") (pintype "passive"))
      (node (ref "C3") (pin "2") (pinfunction "2_2") (pintype "passive"))
      (node (ref "C6") (pin "2") (pinfunction "2_2") (pintype "passive"))
      (node (ref "C7") (pin "2") (pinfunction "2_2") (pintype "passive"))
      (node (ref "C8") (pin "2") (pinfunction "2_2") (pintype "passive"))
      (node (ref "IC2") (pin "1") (pinfunction "VIN_1") (pintype "input"))
      (node (ref "IC2") (pin "3") (pinfunction "CE_3") (pintype "input"))
      (node (ref "PL5") (pin "2") (pinfunction "S_2") (pintype "passive"))
      (node (ref "R17") (pin "1") (pinfunction "1_1") (pintype "passive"))
      (node (ref "U$2") (pin "7") (pinfunction "VIN_7") (pintype "passive"))
      (node (ref "U$3") (pin "7") (pinfunction "VIN_7") (pintype "passive"))
      (node (ref "U$4") (pin "7") (pinfunction "VIN_7") (pintype "passive"))
    )
    (net (code "36") (name "VOUT_6") (class "Default")
      (node (ref "C10") (pin "1") (pinfunction "+_1") (pintype "passive"))
      (node (ref "J6") (pin "1") (pinfunction "S_1") (pintype "passive"))
      (node (ref "J7") (pin "1") (pinfunction "S_1") (pintype "passive"))
      (node (ref "J8") (pin "1") (pinfunction "S_1") (pintype "passive"))
      (node (ref "J9") (pin "1") (pinfunction "S_1") (pintype "passive"))
      (node (ref "L2") (pin "2") (pinfunction "2_2") (pintype "passive"))
      (node (ref "R5") (pin "2") (pinfunction "2_2") (pintype "passive"))
      (node (ref "R7") (pin "2") (pinfunction "2_2") (pintype "passive"))
    )
    (net (code "37") (name "VOUT_MOTOR") (class "Default")
      (node (ref "C16") (pin "1") (pinfunction "+_1") (pintype "passive"))
      (node (ref "J1") (pin "2") (pinfunction "S_2") (pintype "passive"))
      (node (ref "J1") (pin "3") (pinfunction "S_3") (pintype "passive"))
      (node (ref "L3") (pin "2") (pinfunction "2_2") (pintype "passive"))
      (node (ref "R10") (pin "2") (pinfunction "2_2") (pintype "passive"))
      (node (ref "R8") (pin "2") (pinfunction "2_2") (pintype "passive"))
    )
    (net (code "38") (name "VPP{slash}MCLR") (class "Default")
      (node (ref "J11") (pin "7") (pinfunction "P$7_7") (pintype "power_in"))
      (node (ref "J11") (pin "8") (pinfunction "P$8_8") (pintype "power_in"))
      (node (ref "R14") (pin "2") (pinfunction "2_2") (pintype "passive"))
      (node (ref "U$6") (pin "4") (pinfunction "RA3/~{MCLR/VPP}_4") (pintype "bidirectional"))
    )
    (net (code "39") (name "unconnected-(IC2-CB-Pad4)") (class "Default")
      (node (ref "IC2") (pin "4") (pinfunction "CB_4") (pintype "input"))
    )
    (net (code "40") (name "unconnected-(U$1A-GPIO_8-PadP8.35)") (class "Default")
      (node (ref "U$1") (pin "P8.35") (pinfunction "GPIO_8_P8.35") (pintype "bidirectional"))
    )
    (net (code "41") (name "unconnected-(U$1A-GPIO_9-PadP8.33)") (class "Default")
      (node (ref "U$1") (pin "P8.33") (pinfunction "GPIO_9_P8.33") (pintype "bidirectional"))
    )
    (net (code "42") (name "unconnected-(U$1A-GPIO_10-PadP8.31)") (class "Default")
      (node (ref "U$1") (pin "P8.31") (pinfunction "GPIO_10_P8.31") (pintype "bidirectional"))
    )
    (net (code "43") (name "unconnected-(U$1A-GPIO_11-PadP8.32)") (class "Default")
      (node (ref "U$1") (pin "P8.32") (pinfunction "GPIO_11_P8.32") (pintype "bidirectional"))
    )
    (net (code "44") (name "unconnected-(U$1A-GPIO_22-PadP8.19)") (class "Default")
      (node (ref "U$1") (pin "P8.19") (pinfunction "GPIO_22_P8.19") (pintype "bidirectional"))
    )
    (net (code "45") (name "unconnected-(U$1A-GPIO_23-PadP8.13)") (class "Default")
      (node (ref "U$1") (pin "P8.13") (pinfunction "GPIO_23_P8.13") (pintype "bidirectional"))
    )
    (net (code "46") (name "unconnected-(U$1A-GPIO_26-PadP8.14)") (class "Default")
      (node (ref "U$1") (pin "P8.14") (pinfunction "GPIO_26_P8.14") (pintype "bidirectional"))
    )
    (net (code "47") (name "unconnected-(U$1A-GPIO_27-PadP8.17)") (class "Default")
      (node (ref "U$1") (pin "P8.17") (pinfunction "GPIO_27_P8.17") (pintype "bidirectional"))
    )
    (net (code "48") (name "unconnected-(U$1A-GPIO_32-PadP8.25)") (class "Default")
      (node (ref "U$1") (pin "P8.25") (pinfunction "GPIO_32_P8.25") (pintype "bidirectional"))
    )
    (net (code "49") (name "unconnected-(U$1A-GPIO_33-PadP8.24)") (class "Default")
      (node (ref "U$1") (pin "P8.24") (pinfunction "GPIO_33_P8.24") (pintype "bidirectional"))
    )
    (net (code "50") (name "unconnected-(U$1A-GPIO_34-PadP8.5)") (class "Default")
      (node (ref "U$1") (pin "P8.5") (pinfunction "GPIO_34_P8.5") (pintype "bidirectional"))
    )
    (net (code "51") (name "unconnected-(U$1A-GPIO_35-PadP8.6)") (class "Default")
      (node (ref "U$1") (pin "P8.6") (pinfunction "GPIO_35_P8.6") (pintype "bidirectional"))
    )
    (net (code "52") (name "unconnected-(U$1A-GPIO_36-PadP8.23)") (class "Default")
      (node (ref "U$1") (pin "P8.23") (pinfunction "GPIO_36_P8.23") (pintype "bidirectional"))
    )
    (net (code "53") (name "unconnected-(U$1A-GPIO_37-PadP8.22)") (class "Default")
      (node (ref "U$1") (pin "P8.22") (pinfunction "GPIO_37_P8.22") (pintype "bidirectional"))
    )
    (net (code "54") (name "unconnected-(U$1A-GPIO_38-PadP8.3)") (class "Default")
      (node (ref "U$1") (pin "P8.3") (pinfunction "GPIO_38_P8.3") (pintype "bidirectional"))
    )
    (net (code "55") (name "unconnected-(U$1A-GPIO_39-PadP8.4)") (class "Default")
      (node (ref "U$1") (pin "P8.4") (pinfunction "GPIO_39_P8.4") (pintype "bidirectional"))
    )
    (net (code "56") (name "unconnected-(U$1A-GPIO_44-PadP8.12)") (class "Default")
      (node (ref "U$1") (pin "P8.12") (pinfunction "GPIO_44_P8.12") (pintype "bidirectional"))
    )
    (net (code "57") (name "unconnected-(U$1A-GPIO_45-PadP8.11)") (class "Default")
      (node (ref "U$1") (pin "P8.11") (pinfunction "GPIO_45_P8.11") (pintype "bidirectional"))
    )
    (net (code "58") (name "unconnected-(U$1A-GPIO_46-PadP8.16)") (class "Default")
      (node (ref "U$1") (pin "P8.16") (pinfunction "GPIO_46_P8.16") (pintype "bidirectional"))
    )
    (net (code "59") (name "unconnected-(U$1A-GPIO_47-PadP8.15)") (class "Default")
      (node (ref "U$1") (pin "P8.15") (pinfunction "GPIO_47_P8.15") (pintype "bidirectional"))
    )
    (net (code "60") (name "unconnected-(U$1A-GPIO_61-PadP8.26)") (class "Default")
      (node (ref "U$1") (pin "P8.26") (pinfunction "GPIO_61_P8.26") (pintype "bidirectional"))
    )
    (net (code "61") (name "unconnected-(U$1A-GPIO_62-PadP8.21)") (class "Default")
      (node (ref "U$1") (pin "P8.21") (pinfunction "GPIO_62_P8.21") (pintype "bidirectional"))
    )
    (net (code "62") (name "unconnected-(U$1A-GPIO_63-PadP8.20)") (class "Default")
      (node (ref "U$1") (pin "P8.20") (pinfunction "GPIO_63_P8.20") (pintype "bidirectional"))
    )
    (net (code "63") (name "unconnected-(U$1A-GPIO_65-PadP8.18)") (class "Default")
      (node (ref "U$1") (pin "P8.18") (pinfunction "GPIO_65_P8.18") (pintype "bidirectional"))
    )
    (net (code "64") (name "unconnected-(U$1A-GPIO_68-PadP8.10)") (class "Default")
      (node (ref "U$1") (pin "P8.10") (pinfunction "GPIO_68_P8.10") (pintype "bidirectional"))
    )
    (net (code "65") (name "unconnected-(U$1A-GPIO_69-PadP8.9)") (class "Default")
      (node (ref "U$1") (pin "P8.9") (pinfunction "GPIO_69_P8.9") (pintype "bidirectional"))
    )
    (net (code "66") (name "unconnected-(U$1A-GPIO_70-PadP8.45)") (class "Default")
      (node (ref "U$1") (pin "P8.45") (pinfunction "GPIO_70_P8.45") (pintype "bidirectional"))
    )
    (net (code "67") (name "unconnected-(U$1A-GPIO_71-PadP8.46)") (class "Default")
      (node (ref "U$1") (pin "P8.46") (pinfunction "GPIO_71_P8.46") (pintype "bidirectional"))
    )
    (net (code "68") (name "unconnected-(U$1A-GPIO_72-PadP8.43)") (class "Default")
      (node (ref "U$1") (pin "P8.43") (pinfunction "GPIO_72_P8.43") (pintype "bidirectional"))
    )
    (net (code "69") (name "unconnected-(U$1A-GPIO_73-PadP8.44)") (class "Default")
      (node (ref "U$1") (pin "P8.44") (pinfunction "GPIO_73_P8.44") (pintype "bidirectional"))
    )
    (net (code "70") (name "unconnected-(U$1A-GPIO_74-PadP8.41)") (class "Default")
      (node (ref "U$1") (pin "P8.41") (pinfunction "GPIO_74_P8.41") (pintype "bidirectional"))
    )
    (net (code "71") (name "unconnected-(U$1A-GPIO_75-PadP8.42)") (class "Default")
      (node (ref "U$1") (pin "P8.42") (pinfunction "GPIO_75_P8.42") (pintype "bidirectional"))
    )
    (net (code "72") (name "unconnected-(U$1A-GPIO_76-PadP8.39)") (class "Default")
      (node (ref "U$1") (pin "P8.39") (pinfunction "GPIO_76_P8.39") (pintype "bidirectional"))
    )
    (net (code "73") (name "unconnected-(U$1A-GPIO_77-PadP8.40)") (class "Default")
      (node (ref "U$1") (pin "P8.40") (pinfunction "GPIO_77_P8.40") (pintype "bidirectional"))
    )
    (net (code "74") (name "unconnected-(U$1A-GPIO_78-PadP8.37)") (class "Default")
      (node (ref "U$1") (pin "P8.37") (pinfunction "GPIO_78_P8.37") (pintype "bidirectional"))
    )
    (net (code "75") (name "unconnected-(U$1A-GPIO_79-PadP8.38)") (class "Default")
      (node (ref "U$1") (pin "P8.38") (pinfunction "GPIO_79_P8.38") (pintype "bidirectional"))
    )
    (net (code "76") (name "unconnected-(U$1A-GPIO_80-PadP8.36)") (class "Default")
      (node (ref "U$1") (pin "P8.36") (pinfunction "GPIO_80_P8.36") (pintype "bidirectional"))
    )
    (net (code "77") (name "unconnected-(U$1A-GPIO_81-PadP8.34)") (class "Default")
      (node (ref "U$1") (pin "P8.34") (pinfunction "GPIO_81_P8.34") (pintype "bidirectional"))
    )
    (net (code "78") (name "unconnected-(U$1A-GPIO_86-PadP8.27)") (class "Default")
      (node (ref "U$1") (pin "P8.27") (pinfunction "GPIO_86_P8.27") (pintype "bidirectional"))
    )
    (net (code "79") (name "unconnected-(U$1A-GPIO_87-PadP8.29)") (class "Default")
      (node (ref "U$1") (pin "P8.29") (pinfunction "GPIO_87_P8.29") (pintype "bidirectional"))
    )
    (net (code "80") (name "unconnected-(U$1A-GPIO_88-PadP8.28)") (class "Default")
      (node (ref "U$1") (pin "P8.28") (pinfunction "GPIO_88_P8.28") (pintype "bidirectional"))
    )
    (net (code "81") (name "unconnected-(U$1A-GPIO_89-PadP8.30)") (class "Default")
      (node (ref "U$1") (pin "P8.30") (pinfunction "GPIO_89_P8.30") (pintype "bidirectional"))
    )
    (net (code "82") (name "unconnected-(U$1B-AIN0-PadP9.39)") (class "Default")
      (node (ref "U$1") (pin "P9.39") (pinfunction "AIN0_P9.39") (pintype "bidirectional"))
    )
    (net (code "83") (name "unconnected-(U$1B-AIN1-PadP9.40)") (class "Default")
      (node (ref "U$1") (pin "P9.40") (pinfunction "AIN1_P9.40") (pintype "bidirectional"))
    )
    (net (code "84") (name "unconnected-(U$1B-AIN2-PadP9.37)") (class "Default")
      (node (ref "U$1") (pin "P9.37") (pinfunction "AIN2_P9.37") (pintype "bidirectional"))
    )
    (net (code "85") (name "unconnected-(U$1B-AIN3-PadP9.38)") (class "Default")
      (node (ref "U$1") (pin "P9.38") (pinfunction "AIN3_P9.38") (pintype "bidirectional"))
    )
    (net (code "86") (name "unconnected-(U$1B-AIN4-PadP9.33)") (class "Default")
      (node (ref "U$1") (pin "P9.33") (pinfunction "AIN4_P9.33") (pintype "bidirectional"))
    )
    (net (code "87") (name "unconnected-(U$1B-AIN5-PadP9.36)") (class "Default")
      (node (ref "U$1") (pin "P9.36") (pinfunction "AIN5_P9.36") (pintype "bidirectional"))
    )
    (net (code "88") (name "unconnected-(U$1B-AIN6-PadP9.35)") (class "Default")
      (node (ref "U$1") (pin "P9.35") (pinfunction "AIN6_P9.35") (pintype "bidirectional"))
    )
    (net (code "89") (name "unconnected-(U$1B-GNDA_ADC-PadP9.34)") (class "Default")
      (node (ref "U$1") (pin "P9.34") (pinfunction "GNDA_ADC_P9.34") (pintype "bidirectional"))
    )
    (net (code "90") (name "unconnected-(U$1B-GPIO_2-PadP9.22)") (class "Default")
      (node (ref "U$1") (pin "P9.22") (pinfunction "GPIO_2_P9.22") (pintype "bidirectional"))
    )
    (net (code "91") (name "unconnected-(U$1B-GPIO_3-PadP9.21)") (class "Default")
      (node (ref "U$1") (pin "P9.21") (pinfunction "GPIO_3_P9.21") (pintype "bidirectional"))
    )
    (net (code "92") (name "unconnected-(U$1B-GPIO_4-PadP9.17)") (class "Default")
      (node (ref "U$1") (pin "P9.17") (pinfunction "GPIO_4_P9.17") (pintype "bidirectional"))
    )
    (net (code "93") (name "unconnected-(U$1B-GPIO_5-PadP9.18)") (class "Default")
      (node (ref "U$1") (pin "P9.18") (pinfunction "GPIO_5_P9.18") (pintype "bidirectional"))
    )
    (net (code "94") (name "unconnected-(U$1B-GPIO_7-PadP9.42)") (class "Default")
      (node (ref "U$1") (pin "P9.42") (pinfunction "GPIO_7_P9.42") (pintype "bidirectional"))
    )
    (net (code "95") (name "unconnected-(U$1B-GPIO_14-PadP9.26)") (class "Default")
      (node (ref "U$1") (pin "P9.26") (pinfunction "GPIO_14_P9.26") (pintype "bidirectional"))
    )
    (net (code "96") (name "unconnected-(U$1B-GPIO_15-PadP9.24)") (class "Default")
      (node (ref "U$1") (pin "P9.24") (pinfunction "GPIO_15_P9.24") (pintype "bidirectional"))
    )
    (net (code "97") (name "unconnected-(U$1B-GPIO_20-PadP9.41)") (class "Default")
      (node (ref "U$1") (pin "P9.41") (pinfunction "GPIO_20_P9.41") (pintype "bidirectional"))
    )
    (net (code "98") (name "unconnected-(U$1B-GPIO_30-PadP9.11)") (class "Default")
      (node (ref "U$1") (pin "P9.11") (pinfunction "GPIO_30_P9.11") (pintype "bidirectional"))
    )
    (net (code "99") (name "unconnected-(U$1B-GPIO_31-PadP9.13)") (class "Default")
      (node (ref "U$1") (pin "P9.13") (pinfunction "GPIO_31_P9.13") (pintype "bidirectional"))
    )
    (net (code "100") (name "unconnected-(U$1B-GPIO_40-PadP9.14)") (class "Default")
      (node (ref "U$1") (pin "P9.14") (pinfunction "GPIO_40_P9.14") (pintype "bidirectional"))
    )
    (net (code "101") (name "unconnected-(U$1B-GPIO_48-PadP9.15)") (class "Default")
      (node (ref "U$1") (pin "P9.15") (pinfunction "GPIO_48_P9.15") (pintype "bidirectional"))
    )
    (net (code "102") (name "unconnected-(U$1B-GPIO_49-PadP9.23)") (class "Default")
      (node (ref "U$1") (pin "P9.23") (pinfunction "GPIO_49_P9.23") (pintype "bidirectional"))
    )
    (net (code "103") (name "unconnected-(U$1B-GPIO_51-PadP9.16)") (class "Default")
      (node (ref "U$1") (pin "P9.16") (pinfunction "GPIO_51_P9.16") (pintype "bidirectional"))
    )
    (net (code "104") (name "unconnected-(U$1B-GPIO_60-PadP9.12)") (class "Default")
      (node (ref "U$1") (pin "P9.12") (pinfunction "GPIO_60_P9.12") (pintype "bidirectional"))
    )
    (net (code "105") (name "unconnected-(U$1B-GPIO_117-PadP9.25)") (class "Default")
      (node (ref "U$1") (pin "P9.25") (pinfunction "GPIO_117_P9.25") (pintype "bidirectional"))
    )
    (net (code "106") (name "unconnected-(U$1B-GPIO_120-PadP9.31)") (class "Default")
      (node (ref "U$1") (pin "P9.31") (pinfunction "GPIO_120_P9.31") (pintype "bidirectional"))
    )
    (net (code "107") (name "unconnected-(U$1B-GPIO_121-PadP9.29)") (class "Default")
      (node (ref "U$1") (pin "P9.29") (pinfunction "GPIO_121_P9.29") (pintype "bidirectional"))
    )
    (net (code "108") (name "unconnected-(U$1B-GPIO_122-PadP9.30)") (class "Default")
      (node (ref "U$1") (pin "P9.30") (pinfunction "GPIO_122_P9.30") (pintype "bidirectional"))
    )
    (net (code "109") (name "unconnected-(U$1B-GPIO_123-PadP9.28)") (class "Default")
      (node (ref "U$1") (pin "P9.28") (pinfunction "GPIO_123_P9.28") (pintype "bidirectional"))
    )
    (net (code "110") (name "unconnected-(U$1B-GPIO_125-PadP9.27)") (class "Default")
      (node (ref "U$1") (pin "P9.27") (pinfunction "GPIO_125_P9.27") (pintype "bidirectional"))
    )
    (net (code "111") (name "unconnected-(U$1B-I2C2_SCL-PadP9.19)") (class "Default")
      (node (ref "U$1") (pin "P9.19") (pinfunction "I2C2_SCL_P9.19") (pintype "bidirectional"))
    )
    (net (code "112") (name "unconnected-(U$1B-I2C2_SDA-PadP9.20)") (class "Default")
      (node (ref "U$1") (pin "P9.20") (pinfunction "I2C2_SDA_P9.20") (pintype "bidirectional"))
    )
    (net (code "113") (name "unconnected-(U$1B-SYS_5V-PadP9.7)") (class "Default")
      (node (ref "U$1") (pin "P9.7") (pinfunction "SYS_5V_P9.7") (pintype "bidirectional"))
    )
    (net (code "114") (name "unconnected-(U$1B-SYS_5V-PadP9.8)") (class "Default")
      (node (ref "U$1") (pin "P9.8") (pinfunction "SYS_5V_P9.8") (pintype "bidirectional"))
    )
    (net (code "115") (name "unconnected-(U$1B-SYS_RESET~{N}-PadP9.10)") (class "Default")
      (node (ref "U$1") (pin "P9.10") (pinfunction "SYS_RESET~{N}_P9.10") (pintype "bidirectional"))
    )
    (net (code "116") (name "unconnected-(U$1B-VDD_3V3-PadP9.3)") (class "Default")
      (node (ref "U$1") (pin "P9.3") (pinfunction "VDD_3V3_P9.3") (pintype "bidirectional"))
    )
    (net (code "117") (name "unconnected-(U$1B-VDD_3V3-PadP9.4)") (class "Default")
      (node (ref "U$1") (pin "P9.4") (pinfunction "VDD_3V3_P9.4") (pintype "bidirectional"))
    )
    (net (code "118") (name "unconnected-(U$1B-VDD_ADC-PadP9.32)") (class "Default")
      (node (ref "U$1") (pin "P9.32") (pinfunction "VDD_ADC_P9.32") (pintype "bidirectional"))
    )
    (net (code "119") (name "unconnected-(U$6-RC2{slash}AN6-Pad8)") (class "Default")
      (node (ref "U$6") (pin "8") (pinfunction "RC2/AN6_8") (pintype "bidirectional"))
    )
  )
)
